# DIGISPARK.net
KiCad netlist of a schematic drawn in EAGLE
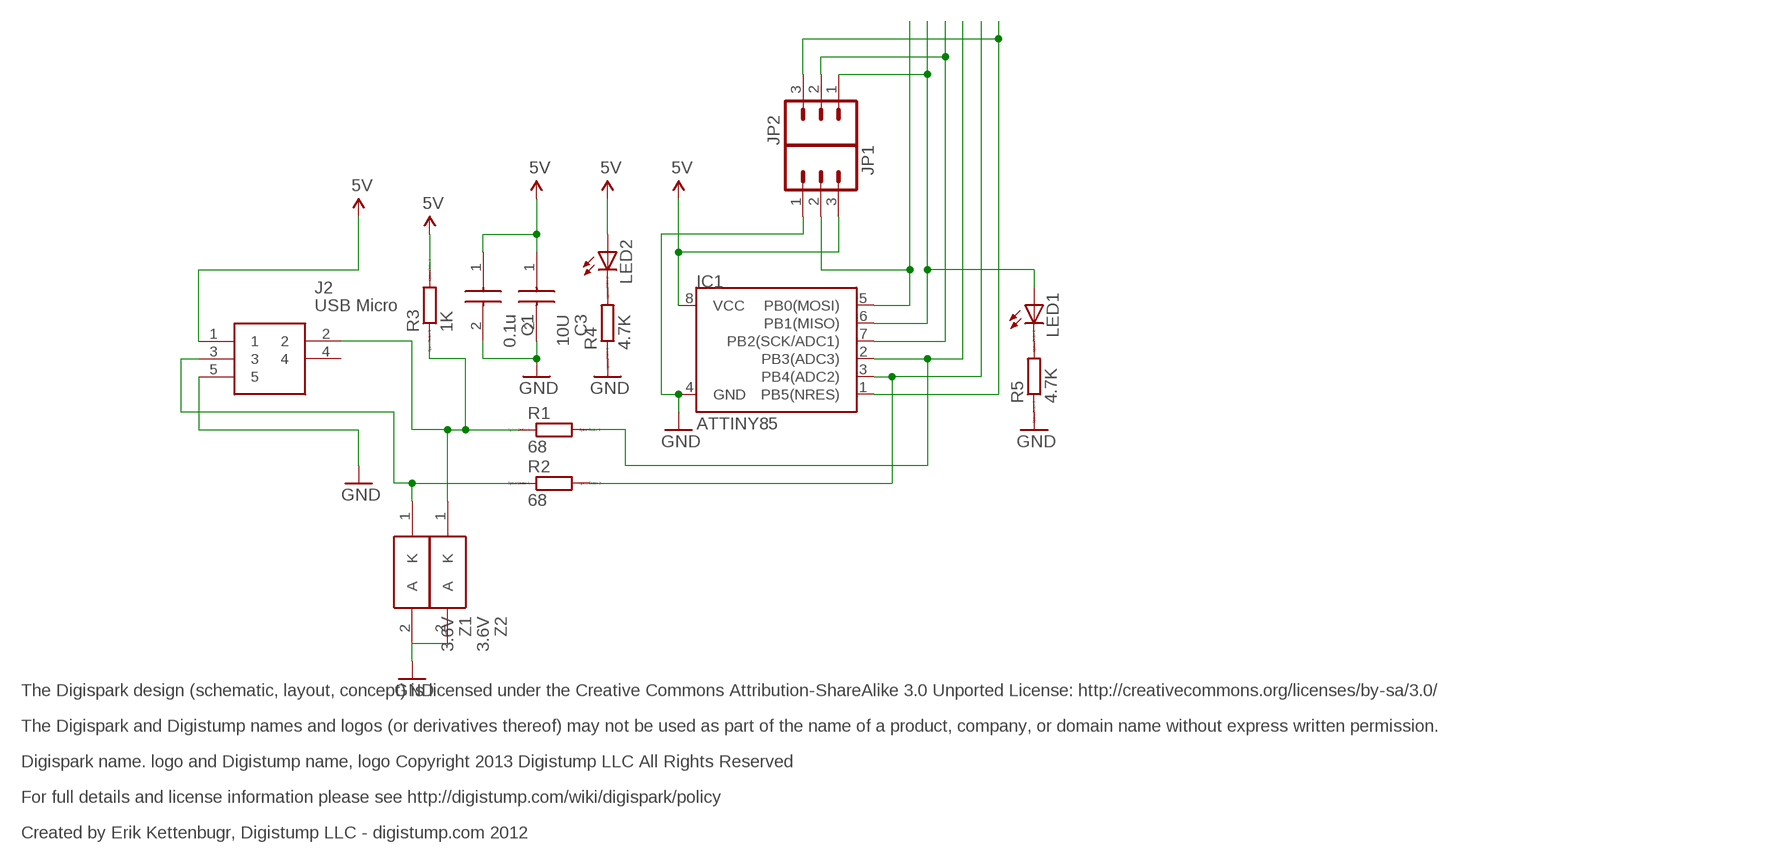
[diagram p0: schematic, sheet 1]

(export (version "E")
  (design (tool "Eeschema 10.0.6"))
  (components
    (comp (ref "C1")
      (value "0.1u")
      (footprint "eagle-import:CAPC2012X70N")
      (fields
        (field (name "ARROW_PART_NUMBER") "GRM2165C1H220JZ01D")
        (field (name "RS_PART_NUMBER") "7236243")
      )
      (libsource (lib "eagle-import") (part "GRM2165C1H220JZ01D"))
    )
    (comp (ref "C3")
      (value "10U")
      (footprint "eagle-import:CAPC2012X70N")
      (fields
        (field (name "ARROW_PART_NUMBER") "GRM2165C1H220JZ01D")
        (field (name "RS_PART_NUMBER") "7236243")
      )
      (libsource (lib "eagle-import") (part "GRM2165C1H220JZ01D"))
    )
    (comp (ref "IC1")
      (value "ATTINY85")
      (footprint "eagle-import:SO08-EIAJ")
      (libsource (lib "eagle-import") (part "ATTINY45"))
    )
    (comp (ref "J2")
      (value "USB Micro")
      (footprint "eagle-import:10104110-0001LF")
      (fields (field (name "ARROW_PART_NUMBER") "10104110-0001LF") (field (name "RS_PART_NUMBER") "1738645"))
      (libsource (lib "eagle-import") (part "10104110-0001LF"))
    )
    (comp (ref "JP1")
      (value "M03PTH")
      (footprint "eagle-import:1X03")
      (libsource (lib "eagle-import") (part "M03PTH"))
    )
    (comp (ref "JP2")
      (value "M03PTH")
      (footprint "eagle-import:1X03")
      (libsource (lib "eagle-import") (part "M03PTH"))
    )
    (comp (ref "LED1")
      (value "LEDCHIPLED_0805")
      (footprint "eagle-import:CHIPLED_0805")
      (libsource (lib "eagle-import") (part "LEDCHIPLED_0805"))
    )
    (comp (ref "LED2")
      (value "LEDCHIPLED_0805")
      (footprint "eagle-import:CHIPLED_0805")
      (libsource (lib "eagle-import") (part "LEDCHIPLED_0805"))
    )
    (comp (ref "R1")
      (value "68")
      (footprint "eagle-import:R2012")
      (libsource (lib "eagle-import") (part "RR2012"))
    )
    (comp (ref "R2")
      (value "68")
      (footprint "eagle-import:R2012")
      (libsource (lib "eagle-import") (part "RR2012"))
    )
    (comp (ref "R3")
      (value "1K")
      (footprint "eagle-import:R2012")
      (libsource (lib "eagle-import") (part "RR2012"))
    )
    (comp (ref "R4")
      (value "4.7K")
      (footprint "eagle-import:R2012")
      (libsource (lib "eagle-import") (part "RR2012"))
    )
    (comp (ref "R5")
      (value "4.7K")
      (footprint "eagle-import:R2012")
      (libsource (lib "eagle-import") (part "RR2012"))
    )
    (comp (ref "Z1")
      (value "3.6V")
      (footprint "eagle-import:TUM-D2")
      (fields (field (name "ARROW_PART_NUMBER") "TFZVTR15B") (field (name "RS_PART_NUMBER") "1715293"))
      (libsource (lib "eagle-import") (part "TFZVTR15B"))
    )
    (comp (ref "Z2")
      (value "3.6V")
      (footprint "eagle-import:TUM-D2")
      (fields (field (name "ARROW_PART_NUMBER") "TFZVTR15B") (field (name "RS_PART_NUMBER") "1715293"))
      (libsource (lib "eagle-import") (part "TFZVTR15B"))
    )
  )
  (nets
    (net (code "1") (name "5V") (class "Default")
      (node (ref "C1") (pin "1") (pinfunction "1_1") (pintype "bidirectional"))
      (node (ref "C3") (pin "1") (pinfunction "1_1") (pintype "bidirectional"))
      (node (ref "IC1") (pin "8") (pinfunction "VCC_8") (pintype "bidirectional"))
      (node (ref "J2") (pin "1") (pinfunction "1_1") (pintype "bidirectional"))
      (node (ref "JP1") (pin "3") (pinfunction "3_3") (pintype "passive"))
      (node (ref "LED2") (pin "A") (pinfunction "A_A") (pintype "passive"))
      (node (ref "R3") (pin "2") (pinfunction "2_2") (pintype "passive"))
    )
    (net (code "2") (name "GND") (class "Default")
      (node (ref "C1") (pin "2") (pinfunction "2_2") (pintype "bidirectional"))
      (node (ref "C3") (pin "2") (pinfunction "2_2") (pintype "bidirectional"))
      (node (ref "IC1") (pin "4") (pinfunction "GND_4") (pintype "bidirectional"))
      (node (ref "J2") (pin "5") (pinfunction "5_5") (pintype "bidirectional"))
      (node (ref "JP1") (pin "1") (pinfunction "1_1") (pintype "passive"))
      (node (ref "R4") (pin "1") (pinfunction "1_1") (pintype "passive"))
      (node (ref "R5") (pin "1") (pinfunction "1_1") (pintype "passive"))
      (node (ref "Z1") (pin "2") (pinfunction "A_2") (pintype "bidirectional"))
      (node (ref "Z2") (pin "2") (pinfunction "A_2") (pintype "bidirectional"))
    )
    (net (code "3") (name "Net-(IC1-PB0(MOSI))") (class "Default")
      (node (ref "IC1") (pin "5") (pinfunction "PB0(MOSI)_5") (pintype "bidirectional"))
      (node (ref "JP1") (pin "2") (pinfunction "2_2") (pintype "passive"))
    )
    (net (code "4") (name "Net-(IC1-PB1(MISO))") (class "Default")
      (node (ref "IC1") (pin "6") (pinfunction "PB1(MISO)_6") (pintype "bidirectional"))
      (node (ref "JP2") (pin "1") (pinfunction "1_1") (pintype "passive"))
      (node (ref "LED1") (pin "A") (pinfunction "A_A") (pintype "passive"))
    )
    (net (code "5") (name "Net-(IC1-PB2(SCK{slash}ADC1))") (class "Default")
      (node (ref "IC1") (pin "7") (pinfunction "PB2(SCK/ADC1)_7") (pintype "bidirectional"))
      (node (ref "JP2") (pin "2") (pinfunction "2_2") (pintype "passive"))
    )
    (net (code "6") (name "Net-(IC1-PB3(ADC3))") (class "Default")
      (node (ref "IC1") (pin "2") (pinfunction "PB3(ADC3)_2") (pintype "bidirectional"))
      (node (ref "R1") (pin "2") (pinfunction "2_2") (pintype "passive"))
    )
    (net (code "7") (name "Net-(IC1-PB4(ADC2))") (class "Default")
      (node (ref "IC1") (pin "3") (pinfunction "PB4(ADC2)_3") (pintype "bidirectional"))
      (node (ref "R2") (pin "2") (pinfunction "2_2") (pintype "passive"))
    )
    (net (code "8") (name "Net-(IC1-PB5(NRES))") (class "Default")
      (node (ref "IC1") (pin "1") (pinfunction "PB5(NRES)_1") (pintype "bidirectional"))
      (node (ref "JP2") (pin "3") (pinfunction "3_3") (pintype "passive"))
    )
    (net (code "9") (name "Net-(LED1-PadC)") (class "Default")
      (node (ref "LED1") (pin "C") (pinfunction "C_C") (pintype "passive"))
      (node (ref "R5") (pin "2") (pinfunction "2_2") (pintype "passive"))
    )
    (net (code "10") (name "Net-(LED2-PadC)") (class "Default")
      (node (ref "LED2") (pin "C") (pinfunction "C_C") (pintype "passive"))
      (node (ref "R4") (pin "2") (pinfunction "2_2") (pintype "passive"))
    )
    (net (code "11") (name "Net-(Z1-K)") (class "Default")
      (node (ref "J2") (pin "3") (pinfunction "3_3") (pintype "bidirectional"))
      (node (ref "R2") (pin "1") (pinfunction "1_1") (pintype "passive"))
      (node (ref "Z1") (pin "1") (pinfunction "K_1") (pintype "bidirectional"))
    )
    (net (code "12") (name "Net-(Z2-K)") (class "Default")
      (node (ref "J2") (pin "2") (pinfunction "2_2") (pintype "bidirectional"))
      (node (ref "R1") (pin "1") (pinfunction "1_1") (pintype "passive"))
      (node (ref "R3") (pin "1") (pinfunction "1_1") (pintype "passive"))
      (node (ref "Z2") (pin "1") (pinfunction "K_1") (pintype "bidirectional"))
    )
    (net (code "13") (name "unconnected-(J2-Pad4)") (class "Default")
      (node (ref "J2") (pin "4") (pinfunction "4_4") (pintype "bidirectional"))
    )
  )
)
